# CAN.net
KiCad netlist of a schematic drawn in Altium Designer
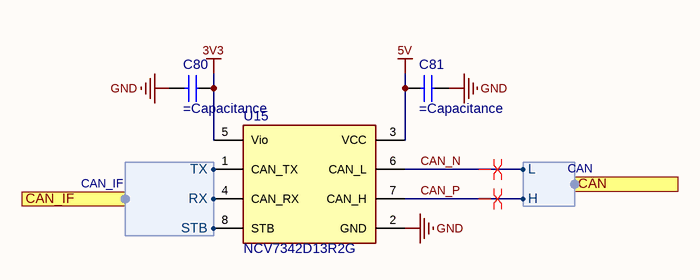
[diagram p0: CAN.SchDoc]

(export (version "E")
  (design (tool "Eeschema 10.0.6"))
  (components
    (comp (ref "C80")
      (value "~")
      (footprint "C0402")
      (description "CAP CER 0.1UF 50V X7R 0402")
      (fields
        (field (name "MANUFACTURER") "Walsin Technologies")
        (field (name "MANUFACTURER PART NUMBER") "0402B104K500CT")
      )
      (libsource (lib "Capacitors") (part "CAP0402-0.1uF-50V"))
    )
    (comp (ref "C81")
      (value "~")
      (footprint "C0402")
      (description "CAP CER 0.1UF 50V X7R 0402")
      (fields
        (field (name "MANUFACTURER") "Walsin Technologies")
        (field (name "MANUFACTURER PART NUMBER") "0402B104K500CT")
      )
      (libsource (lib "Capacitors") (part "CAP0402-0.1uF-50V"))
    )
    (comp (ref "U15")
      (value "NCV7342D13R2G")
      (footprint "SOIC8")
      (description "IC TRANSCEIVER HALF 1/1 8SOIC")
      (fields (field (name "MANUFACTURER") "ON Semiconductor"))
      (libsource (lib "IC") (part "NCV7342D13R2G"))
    )
  )
  (nets
    (net (code "3") (name "/CAN_N") (class "Default")
      (node (ref "U15") (pin "6") (pinfunction "CAN_L_6") (pintype "passive"))
    )
    (net (code "4") (name "/CAN_P") (class "Default")
      (node (ref "U15") (pin "7") (pinfunction "CAN_H_7") (pintype "passive"))
    )
    (net (code "5") (name "/RX") (class "Default")
      (node (ref "U15") (pin "4") (pinfunction "CAN_RX_4") (pintype "passive"))
    )
    (net (code "6") (name "/STB") (class "Default")
      (node (ref "U15") (pin "8") (pinfunction "STB_8") (pintype "passive"))
    )
    (net (code "7") (name "/TX") (class "Default")
      (node (ref "U15") (pin "1") (pinfunction "CAN_TX_1") (pintype "passive"))
    )
    (net (code "10") (name "3V3") (class "Default")
      (node (ref "C80") (pin "1") (pinfunction "1_1") (pintype "passive"))
      (node (ref "U15") (pin "5") (pinfunction "Vio_5") (pintype "passive"))
    )
    (net (code "11") (name "5V") (class "Default")
      (node (ref "C81") (pin "2") (pinfunction "2_2") (pintype "passive"))
      (node (ref "U15") (pin "3") (pinfunction "VCC_3") (pintype "passive"))
    )
    (net (code "12") (name "GND") (class "Default")
      (node (ref "C80") (pin "2") (pinfunction "2_2") (pintype "passive"))
      (node (ref "C81") (pin "1") (pinfunction "1_1") (pintype "passive"))
      (node (ref "U15") (pin "2") (pinfunction "GND_2") (pintype "passive"))
    )
  )
)
